# PWR_N5V5.net
KiCad netlist of a schematic drawn in Altium Designer
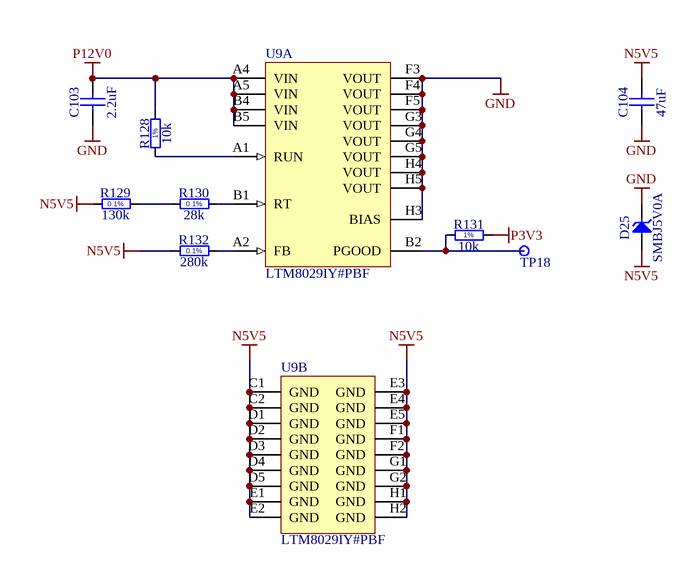
[diagram p0: PWR_N5V5.SchDoc]

(export (version "E")
  (design (tool "Eeschema 10.0.6"))
  (components
    (comp (ref "C103")
      (value "2.2uF")
      (footprint "CAPC2012X140N")
      (description "Non-polarised capacitor")
      (fields
        (field (name "PART NUMBER") "CC0805_2.2UF_50V_10%_X7R")
        (field (name "VOLTAGE") "50V")
        (field (name "AUTHOR") "CERN DEM JLC")
      )
      (libsource (lib "Capacitors") (part "Capacitor - non polarized"))
    )
    (comp (ref "C104")
      (value "47uF")
      (footprint "CAPC3216X180N")
      (description "Non-polarised capacitor")
      (fields
        (field (name "PART NUMBER") "CC1206_47UF_10V_10%_X5R")
        (field (name "VOLTAGE") "10V")
        (field (name "AUTHOR") "CERN DEM MR")
      )
      (libsource (lib "Capacitors") (part "Capacitor - non polarized"))
    )
    (comp (ref "D25")
      (value "SMBJ5V0A")
      (footprint "DIOM5336X265N")
      (description "Zener Diode")
      (fields
        (field (name "VOLTAGE") "5V")
        (field (name "POWER") "600W")
        (field (name "AUTHOR") "CERN DEM JLC")
      )
      (libsource (lib "ICs And Semiconductors") (part "Diode Zener"))
    )
    (comp (ref "R128")
      (value "10k")
      (footprint "RESC1005X40N")
      (description "Resistor - 1%")
      (fields
        (field (name "PART NUMBER") "R0402_10K_1%_0.0625W_100PPM")
        (field (name "MANUFACTURER") "GENERIC")
        (field (name "AUTHOR") "CERN DEM JLC")
      )
      (libsource (lib "Resistors") (part "Resistor - 1%"))
    )
    (comp (ref "R129")
      (value "130k")
      (footprint "RESC1608X55N")
      (description "Resistor - 0.1%")
      (fields
        (field (name "PART NUMBER") "R0603_130K_0.1%_0.063W_10PPM")
        (field (name "POWER") "0.063W")
        (field (name "AUTHOR") "CERN DEM JLC")
      )
      (libsource (lib "Resistors") (part "Resistor - 0.1%"))
    )
    (comp (ref "R130")
      (value "28k")
      (footprint "RESC1608X55N")
      (description "Resistor - 0.1%")
      (fields
        (field (name "PART NUMBER") "R0603_28K_0.1%_0.063W_10PPM")
        (field (name "POWER") "0.063W")
        (field (name "AUTHOR") "CERN DEM JLC")
      )
      (libsource (lib "Resistors") (part "Resistor - 0.1%"))
    )
    (comp (ref "R131")
      (value "10k")
      (footprint "RESC1005X40N")
      (description "Resistor - 1%")
      (fields
        (field (name "PART NUMBER") "R0402_10K_1%_0.0625W_100PPM")
        (field (name "MANUFACTURER") "GENERIC")
        (field (name "AUTHOR") "CERN DEM JLC")
      )
      (libsource (lib "Resistors") (part "Resistor - 1%"))
    )
    (comp (ref "R132")
      (value "280k")
      (footprint "RESC1608X55N")
      (description "Resistor - 0.1%")
      (fields
        (field (name "PART NUMBER") "R0603_280K_0.1%_0.063W_10PPM")
        (field (name "POWER") "0.063W")
        (field (name "AUTHOR") "CERN DEM BC")
      )
      (libsource (lib "Resistors") (part "Resistor - 0.1%"))
    )
    (comp (ref "TP18")
      (value "Test Point")
      (footprint "TPS127")
      (fields (field (name "PART NUMBER") "SMD_PAD_1.27X1.27MM") (field (name "AUTHOR") "CERN DEM JLC"))
      (libsource (lib "Eletro-mechanical") (part "Test Point"))
    )
    (comp (ref "U9")
      (value "LTM8029IY#PBF")
      (footprint "LT-BGA-35-11250X6250X3420")
      (fields (field (name "MANUFACTURER") "Linear Technology"))
      (libsource (lib "Altium Content Vault") (part "LT-LTM8029-BGA-35"))
    )
  )
  (nets
    (net (code "1") (name "GND") (class "Default")
      (node (ref "C103") (pin "1") (pinfunction "1_1") (pintype "passive"))
      (node (ref "C104") (pin "1") (pinfunction "1_1") (pintype "passive"))
      (node (ref "D25") (pin "1") (pinfunction "C_1") (pintype "passive"))
      (node (ref "U9") (pin "F3") (pinfunction "VOUT_F3") (pintype "power_in"))
      (node (ref "U9") (pin "F4") (pinfunction "VOUT_F4") (pintype "power_in"))
      (node (ref "U9") (pin "F5") (pinfunction "VOUT_F5") (pintype "power_in"))
      (node (ref "U9") (pin "G3") (pinfunction "VOUT_G3") (pintype "power_in"))
      (node (ref "U9") (pin "G4") (pinfunction "VOUT_G4") (pintype "power_in"))
      (node (ref "U9") (pin "G5") (pinfunction "VOUT_G5") (pintype "power_in"))
      (node (ref "U9") (pin "H3") (pinfunction "BIAS_H3") (pintype "power_in"))
      (node (ref "U9") (pin "H4") (pinfunction "VOUT_H4") (pintype "power_in"))
      (node (ref "U9") (pin "H5") (pinfunction "VOUT_H5") (pintype "power_in"))
    )
    (net (code "2") (name "N5V5") (class "Default")
      (node (ref "C104") (pin "2") (pinfunction "2_2") (pintype "passive"))
      (node (ref "D25") (pin "2") (pinfunction "A_2") (pintype "passive"))
      (node (ref "R129") (pin "1") (pinfunction "1_1") (pintype "passive"))
      (node (ref "R132") (pin "1") (pinfunction "1_1") (pintype "passive"))
      (node (ref "U9") (pin "C1") (pinfunction "GND_C1") (pintype "power_in"))
      (node (ref "U9") (pin "C2") (pinfunction "GND_C2") (pintype "power_in"))
      (node (ref "U9") (pin "D1") (pinfunction "GND_D1") (pintype "power_in"))
      (node (ref "U9") (pin "D2") (pinfunction "GND_D2") (pintype "power_in"))
      (node (ref "U9") (pin "D3") (pinfunction "GND_D3") (pintype "power_in"))
      (node (ref "U9") (pin "D4") (pinfunction "GND_D4") (pintype "power_in"))
      (node (ref "U9") (pin "D5") (pinfunction "GND_D5") (pintype "power_in"))
      (node (ref "U9") (pin "E1") (pinfunction "GND_E1") (pintype "power_in"))
      (node (ref "U9") (pin "E2") (pinfunction "GND_E2") (pintype "power_in"))
      (node (ref "U9") (pin "E3") (pinfunction "GND_E3") (pintype "power_in"))
      (node (ref "U9") (pin "E4") (pinfunction "GND_E4") (pintype "power_in"))
      (node (ref "U9") (pin "E5") (pinfunction "GND_E5") (pintype "power_in"))
      (node (ref "U9") (pin "F1") (pinfunction "GND_F1") (pintype "power_in"))
      (node (ref "U9") (pin "F2") (pinfunction "GND_F2") (pintype "power_in"))
      (node (ref "U9") (pin "G1") (pinfunction "GND_G1") (pintype "power_in"))
      (node (ref "U9") (pin "G2") (pinfunction "GND_G2") (pintype "power_in"))
      (node (ref "U9") (pin "H1") (pinfunction "GND_H1") (pintype "power_in"))
      (node (ref "U9") (pin "H2") (pinfunction "GND_H2") (pintype "power_in"))
    )
    (net (code "3") (name "Net-(R129-Pad2)") (class "Default")
      (node (ref "R129") (pin "2") (pinfunction "2_2") (pintype "passive"))
      (node (ref "R130") (pin "1") (pinfunction "1_1") (pintype "passive"))
    )
    (net (code "4") (name "Net-(U9A-FB)") (class "Default")
      (node (ref "R132") (pin "2") (pinfunction "2_2") (pintype "passive"))
      (node (ref "U9") (pin "A2") (pinfunction "FB_A2") (pintype "input"))
    )
    (net (code "5") (name "Net-(U9A-PGOOD)") (class "Default")
      (node (ref "R131") (pin "1") (pinfunction "1_1") (pintype "passive"))
      (node (ref "TP18") (pin "1") (pinfunction "1_1") (pintype "bidirectional"))
      (node (ref "U9") (pin "B2") (pinfunction "PGOOD_B2") (pintype "open_collector"))
    )
    (net (code "6") (name "Net-(U9A-RT)") (class "Default")
      (node (ref "R130") (pin "2") (pinfunction "2_2") (pintype "passive"))
      (node (ref "U9") (pin "B1") (pinfunction "RT_B1") (pintype "input"))
    )
    (net (code "7") (name "Net-(U9A-RUN)") (class "Default")
      (node (ref "R128") (pin "1") (pinfunction "1_1") (pintype "passive"))
      (node (ref "U9") (pin "A1") (pinfunction "RUN_A1") (pintype "input"))
    )
    (net (code "8") (name "P3V3") (class "Default")
      (node (ref "R131") (pin "2") (pinfunction "2_2") (pintype "passive"))
    )
    (net (code "9") (name "P12V0") (class "Default")
      (node (ref "C103") (pin "2") (pinfunction "2_2") (pintype "passive"))
      (node (ref "R128") (pin "2") (pinfunction "2_2") (pintype "passive"))
      (node (ref "U9") (pin "A4") (pinfunction "VIN_A4") (pintype "power_in"))
      (node (ref "U9") (pin "A5") (pinfunction "VIN_A5") (pintype "power_in"))
      (node (ref "U9") (pin "B4") (pinfunction "VIN_B4") (pintype "power_in"))
      (node (ref "U9") (pin "B5") (pinfunction "VIN_B5") (pintype "power_in"))
    )
  )
)
